# esp12_Epaper4_2.net
KiCad netlist of a schematic drawn in EAGLE
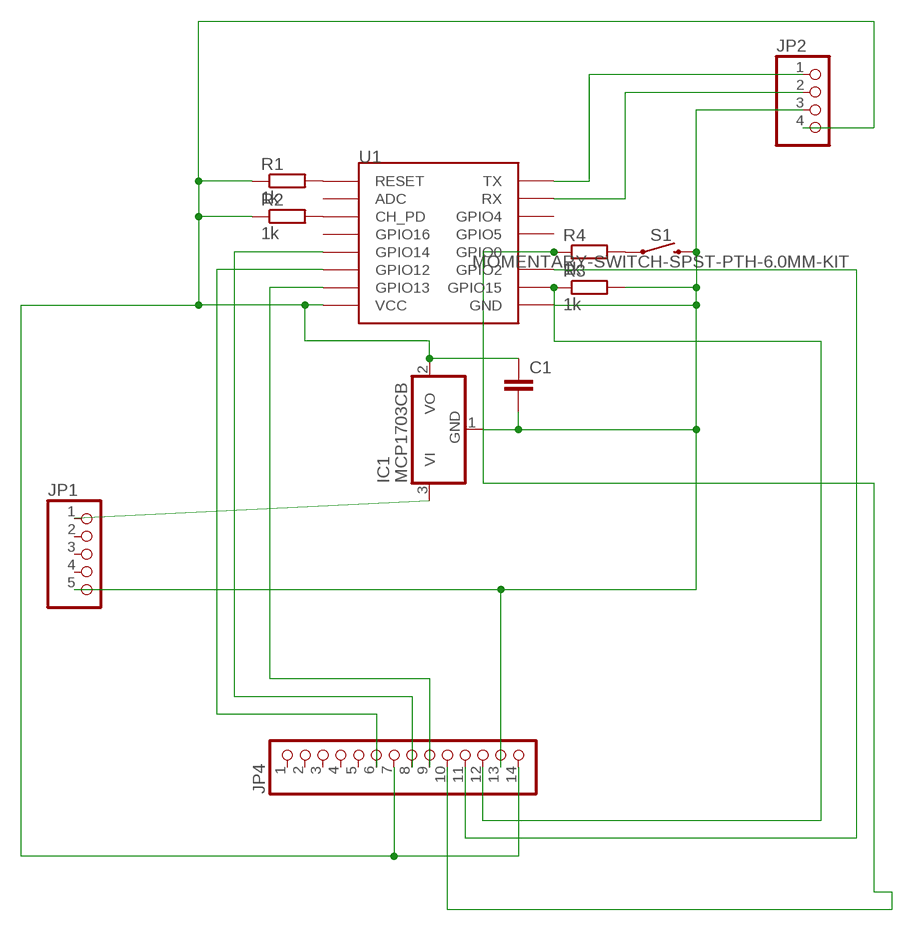
[diagram p0: schematic, sheet 1]

(export (version "E")
  (design (tool "Eeschema 10.0.6"))
  (components
    (comp (ref "C1")
      (value "C-EU025-050X050")
      (footprint "eagle-import:C025-050X050")
      (libsource (lib "eagle-import") (part "C-EU025-050X050"))
    )
    (comp (ref "IC1")
      (value "MCP1703CB")
      (footprint "eagle-import:SOT23")
      (libsource (lib "eagle-import") (part "MCP1703CB"))
    )
    (comp (ref "JP1")
      (value "PINHD-1X5")
      (footprint "eagle-import:1X05")
      (libsource (lib "eagle-import") (part "PINHD-1X5"))
    )
    (comp (ref "JP2")
      (value "PINHD-1X4/90")
      (footprint "eagle-import:1X04_90")
      (libsource (lib "eagle-import") (part "PINHD-1X4/90"))
    )
    (comp (ref "JP4")
      (value "PINHD-1X14")
      (footprint "eagle-import:1X14")
      (libsource (lib "eagle-import") (part "PINHD-1X14"))
    )
    (comp (ref "R1")
      (value "1k")
      (footprint "eagle-import:R1206")
      (libsource (lib "eagle-import") (part "R-EU_R1206"))
    )
    (comp (ref "R2")
      (value "1k")
      (footprint "eagle-import:R1206")
      (libsource (lib "eagle-import") (part "R-EU_R1206"))
    )
    (comp (ref "R3")
      (value "1k")
      (footprint "eagle-import:R1206")
      (libsource (lib "eagle-import") (part "R-EU_R1206"))
    )
    (comp (ref "R4")
      (value "1k")
      (footprint "eagle-import:R1206")
      (libsource (lib "eagle-import") (part "R-EU_R1206"))
    )
    (comp (ref "S1")
      (value "MOMENTARY-SWITCH-SPST-PTH-6.0MM-KIT")
      (footprint "eagle-import:TACTILE_SWITCH_PTH_6.0MM_KIT")
      (libsource (lib "eagle-import") (part "MOMENTARY-SWITCH-SPST-PTH-6.0MM-KIT"))
    )
    (comp (ref "U1")
      (value "ESP12")
      (footprint "eagle-import:ESP12")
      (libsource (lib "eagle-import") (part "ESP12"))
    )
  )
  (nets
    (net (code "1") (name "Net-(IC1-GND)") (class "Default")
      (node (ref "C1") (pin "2") (pinfunction "2_2") (pintype "passive"))
      (node (ref "IC1") (pin "1") (pinfunction "GND_1") (pintype "passive"))
      (node (ref "JP1") (pin "5") (pinfunction "5_5") (pintype "passive"))
      (node (ref "JP2") (pin "3") (pinfunction "3_3") (pintype "passive"))
      (node (ref "JP4") (pin "13") (pinfunction "13_13") (pintype "passive"))
      (node (ref "R3") (pin "2") (pinfunction "2_2") (pintype "passive"))
      (node (ref "S1") (pin "3") (pinfunction "2_3") (pintype "passive"))
      (node (ref "U1") (pin "GND") (pinfunction "GND_GND") (pintype "bidirectional"))
    )
    (net (code "2") (name "Net-(IC1-VI)") (class "Default")
      (node (ref "IC1") (pin "3") (pinfunction "VI_3") (pintype "input"))
      (node (ref "JP1") (pin "1") (pinfunction "1_1") (pintype "passive"))
    )
    (net (code "3") (name "Net-(IC1-VO)") (class "Default")
      (node (ref "C1") (pin "1") (pinfunction "1_1") (pintype "passive"))
      (node (ref "IC1") (pin "2") (pinfunction "VO_2") (pintype "passive"))
      (node (ref "JP2") (pin "4") (pinfunction "4_4") (pintype "passive"))
      (node (ref "JP4") (pin "14") (pinfunction "14_14") (pintype "passive"))
      (node (ref "JP4") (pin "7") (pinfunction "7_7") (pintype "passive"))
      (node (ref "R1") (pin "1") (pinfunction "1_1") (pintype "passive"))
      (node (ref "R2") (pin "1") (pinfunction "1_1") (pintype "passive"))
      (node (ref "U1") (pin "VCC") (pinfunction "VCC_VCC") (pintype "bidirectional"))
    )
    (net (code "4") (name "Net-(JP2-Pad1)") (class "Default")
      (node (ref "JP2") (pin "1") (pinfunction "1_1") (pintype "passive"))
      (node (ref "U1") (pin "TX") (pinfunction "TX_TX") (pintype "bidirectional"))
    )
    (net (code "5") (name "Net-(JP2-Pad2)") (class "Default")
      (node (ref "JP2") (pin "2") (pinfunction "2_2") (pintype "passive"))
      (node (ref "U1") (pin "RX") (pinfunction "RX_RX") (pintype "bidirectional"))
    )
    (net (code "6") (name "Net-(JP4-Pad6)") (class "Default")
      (node (ref "JP4") (pin "6") (pinfunction "6_6") (pintype "passive"))
      (node (ref "U1") (pin "GPIO12") (pinfunction "GPIO12_GPIO12") (pintype "bidirectional"))
    )
    (net (code "7") (name "Net-(JP4-Pad8)") (class "Default")
      (node (ref "JP4") (pin "8") (pinfunction "8_8") (pintype "passive"))
      (node (ref "U1") (pin "GPIO14") (pinfunction "GPIO14_GPIO14") (pintype "bidirectional"))
    )
    (net (code "8") (name "Net-(JP4-Pad9)") (class "Default")
      (node (ref "JP4") (pin "9") (pinfunction "9_9") (pintype "passive"))
      (node (ref "U1") (pin "GPIO13") (pinfunction "GPIO13_GPIO13") (pintype "bidirectional"))
    )
    (net (code "9") (name "Net-(JP4-Pad10)") (class "Default")
      (node (ref "JP4") (pin "10") (pinfunction "10_10") (pintype "passive"))
      (node (ref "R4") (pin "1") (pinfunction "1_1") (pintype "passive"))
      (node (ref "U1") (pin "GPIO0") (pinfunction "GPIO0_GPIO0") (pintype "bidirectional"))
    )
    (net (code "10") (name "Net-(JP4-Pad11)") (class "Default")
      (node (ref "JP4") (pin "11") (pinfunction "11_11") (pintype "passive"))
      (node (ref "U1") (pin "GPIO2") (pinfunction "GPIO2_GPIO2") (pintype "bidirectional"))
    )
    (net (code "11") (name "Net-(JP4-Pad12)") (class "Default")
      (node (ref "JP4") (pin "12") (pinfunction "12_12") (pintype "passive"))
      (node (ref "R3") (pin "1") (pinfunction "1_1") (pintype "passive"))
      (node (ref "U1") (pin "GPIO15") (pinfunction "GPIO15_GPIO15") (pintype "bidirectional"))
    )
    (net (code "12") (name "Net-(R1-Pad2)") (class "Default")
      (node (ref "R1") (pin "2") (pinfunction "2_2") (pintype "passive"))
      (node (ref "U1") (pin "RESET") (pinfunction "RESET_RESET") (pintype "bidirectional"))
    )
    (net (code "13") (name "Net-(R2-Pad2)") (class "Default")
      (node (ref "R2") (pin "2") (pinfunction "2_2") (pintype "passive"))
      (node (ref "U1") (pin "CH_PD") (pinfunction "CH_PD_CH_PD") (pintype "bidirectional"))
    )
    (net (code "14") (name "Net-(R4-Pad2)") (class "Default")
      (node (ref "R4") (pin "2") (pinfunction "2_2") (pintype "passive"))
      (node (ref "S1") (pin "1") (pinfunction "1_1") (pintype "passive"))
    )
    (net (code "15") (name "unconnected-(JP1-Pad2)") (class "Default")
      (node (ref "JP1") (pin "2") (pinfunction "2_2") (pintype "passive"))
    )
    (net (code "16") (name "unconnected-(JP1-Pad3)") (class "Default")
      (node (ref "JP1") (pin "3") (pinfunction "3_3") (pintype "passive"))
    )
    (net (code "17") (name "unconnected-(JP1-Pad4)") (class "Default")
      (node (ref "JP1") (pin "4") (pinfunction "4_4") (pintype "passive"))
    )
    (net (code "18") (name "unconnected-(JP4-Pad1)") (class "Default")
      (node (ref "JP4") (pin "1") (pinfunction "1_1") (pintype "passive"))
    )
    (net (code "19") (name "unconnected-(JP4-Pad2)") (class "Default")
      (node (ref "JP4") (pin "2") (pinfunction "2_2") (pintype "passive"))
    )
    (net (code "20") (name "unconnected-(JP4-Pad3)") (class "Default")
      (node (ref "JP4") (pin "3") (pinfunction "3_3") (pintype "passive"))
    )
    (net (code "21") (name "unconnected-(JP4-Pad4)") (class "Default")
      (node (ref "JP4") (pin "4") (pinfunction "4_4") (pintype "passive"))
    )
    (net (code "22") (name "unconnected-(JP4-Pad5)") (class "Default")
      (node (ref "JP4") (pin "5") (pinfunction "5_5") (pintype "passive"))
    )
    (net (code "23") (name "unconnected-(U1-PadADC)") (class "Default")
      (node (ref "U1") (pin "ADC") (pinfunction "ADC_ADC") (pintype "bidirectional"))
    )
    (net (code "24") (name "unconnected-(U1-PadGPIO4)") (class "Default")
      (node (ref "U1") (pin "GPIO4") (pinfunction "GPIO4_GPIO4") (pintype "bidirectional"))
    )
    (net (code "25") (name "unconnected-(U1-PadGPIO5)") (class "Default")
      (node (ref "U1") (pin "GPIO5") (pinfunction "GPIO5_GPIO5") (pintype "bidirectional"))
    )
    (net (code "26") (name "unconnected-(U1-PadGPIO16)") (class "Default")
      (node (ref "U1") (pin "GPIO16") (pinfunction "GPIO16_GPIO16") (pintype "bidirectional"))
    )
  )
)
